# 08_Peripherals.net
KiCad netlist of a schematic drawn in Altium Designer
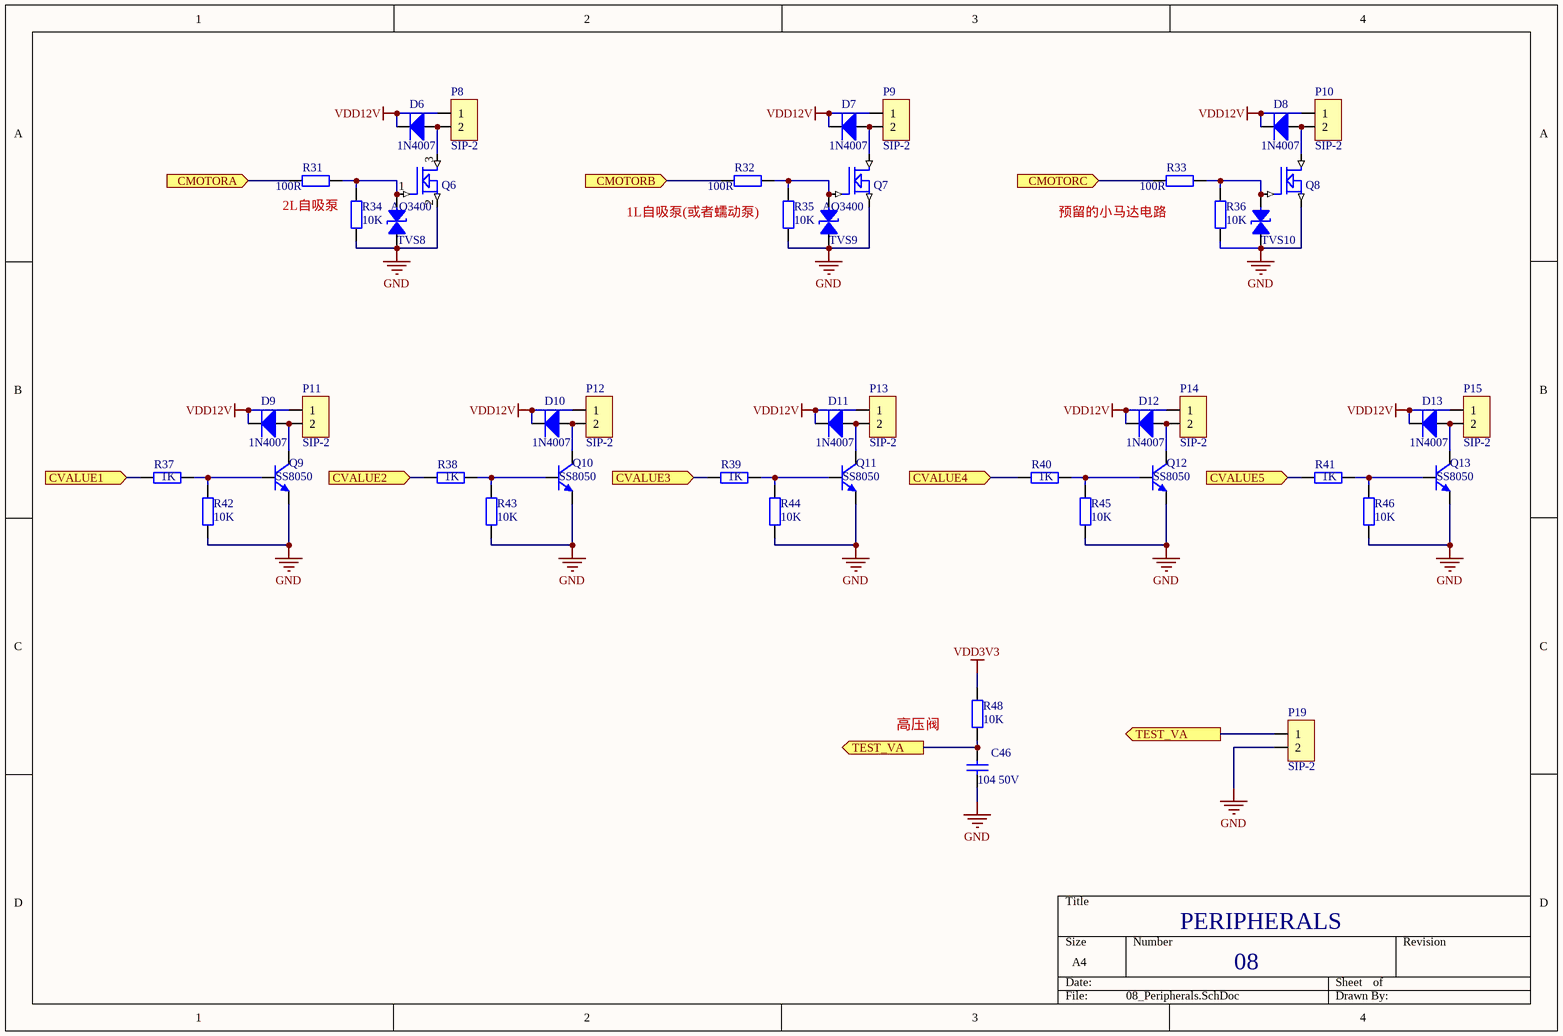
[diagram p0: 08_Peripherals.SchDoc]

(export (version "E")
  (design (tool "Eeschema 10.0.6"))
  (components
    (comp (ref "C46")
      (value "104 50V")
      (footprint "SMD-0603C")
      (description "贴片电容 10%")
      (libsource (lib "XiaoyI") (part "CAP4"))
    )
    (comp (ref "D6")
      (value "1N4007")
      (footprint "DO-214-AC")
      (description "贴片二极管")
      (libsource (lib "XiaoyI") (part "DIODE2"))
    )
    (comp (ref "D7")
      (value "1N4007")
      (footprint "DO-214-AC")
      (description "贴片二极管")
      (libsource (lib "XiaoyI") (part "DIODE2"))
    )
    (comp (ref "D8")
      (value "1N4007")
      (footprint "DO-214-AC")
      (description "贴片二极管")
      (libsource (lib "XiaoyI") (part "DIODE2"))
    )
    (comp (ref "D9")
      (value "1N4007")
      (footprint "DO-214-AC")
      (description "贴片二极管")
      (libsource (lib "XiaoyI") (part "DIODE2"))
    )
    (comp (ref "D10")
      (value "1N4007")
      (footprint "DO-214-AC")
      (description "贴片二极管")
      (libsource (lib "XiaoyI") (part "DIODE2"))
    )
    (comp (ref "D11")
      (value "1N4007")
      (footprint "DO-214-AC")
      (description "贴片二极管")
      (libsource (lib "XiaoyI") (part "DIODE2"))
    )
    (comp (ref "D12")
      (value "1N4007")
      (footprint "DO-214-AC")
      (description "贴片二极管")
      (libsource (lib "XiaoyI") (part "DIODE2"))
    )
    (comp (ref "D13")
      (value "1N4007")
      (footprint "DO-214-AC")
      (description "贴片二极管")
      (libsource (lib "XiaoyI") (part "DIODE2"))
    )
    (comp (ref "P8")
      (value "SIP-2")
      (footprint "XH-2.54-2P-LI")
      (description "XH2.54 2P 立贴")
      (libsource (lib "XiaoyI") (part "SIP-2"))
    )
    (comp (ref "P9")
      (value "SIP-2")
      (footprint "XH-2.54-2P-LI")
      (description "XH2.54 2P 立贴")
      (libsource (lib "XiaoyI") (part "SIP-2"))
    )
    (comp (ref "P10")
      (value "SIP-2")
      (footprint "XH-2.54-2P-LI")
      (description "XH2.54 2P 立贴")
      (libsource (lib "XiaoyI") (part "SIP-2"))
    )
    (comp (ref "P11")
      (value "SIP-2")
      (footprint "XH-2.54-2P-LI")
      (description "XH2.54 2P 立贴")
      (libsource (lib "XiaoyI") (part "SIP-2"))
    )
    (comp (ref "P12")
      (value "SIP-2")
      (footprint "XH-2.54-2P-LI")
      (description "XH2.54 2P 立贴")
      (libsource (lib "XiaoyI") (part "SIP-2"))
    )
    (comp (ref "P13")
      (value "SIP-2")
      (footprint "XH-2.54-2P-LI")
      (description "XH2.54 2P 立贴")
      (libsource (lib "XiaoyI") (part "SIP-2"))
    )
    (comp (ref "P14")
      (value "SIP-2")
      (footprint "XH-2.54-2P-LI")
      (description "XH2.54 2P 立贴")
      (libsource (lib "XiaoyI") (part "SIP-2"))
    )
    (comp (ref "P15")
      (value "SIP-2")
      (footprint "XH-2.54-2P-LI")
      (description "XH2.54 2P 立贴")
      (libsource (lib "XiaoyI") (part "SIP-2"))
    )
    (comp (ref "P19")
      (value "SIP-2")
      (footprint "XH-2.54-2P-LI")
      (description "XH2.54 2P 立贴")
      (libsource (lib "XiaoyI") (part "SIP-2"))
    )
    (comp (ref "Q6")
      (value "AO3400")
      (footprint "SOT-23")
      (description "MOSFET N")
      (libsource (lib "") (part "MOSFET N_1"))
    )
    (comp (ref "Q7")
      (value "AO3400")
      (footprint "SOT-23")
      (description "MOSFET N")
      (libsource (lib "XiaoyI") (part "MOSFET N"))
    )
    (comp (ref "Q8")
      (value "AO3400")
      (footprint "SOT-23")
      (description "MOSFET N")
      (libsource (lib "XiaoyI") (part "MOSFET N"))
    )
    (comp (ref "Q9")
      (value "SS8050")
      (footprint "SOT-23")
      (description "三极管")
      (libsource (lib "XiaoyI") (part "NPN-1"))
    )
    (comp (ref "Q10")
      (value "SS8050")
      (footprint "SOT-23")
      (description "三极管")
      (libsource (lib "XiaoyI") (part "NPN-1"))
    )
    (comp (ref "Q11")
      (value "SS8050")
      (footprint "SOT-23")
      (description "三极管")
      (libsource (lib "XiaoyI") (part "NPN-1"))
    )
    (comp (ref "Q12")
      (value "SS8050")
      (footprint "SOT-23")
      (description "三极管")
      (libsource (lib "XiaoyI") (part "NPN-1"))
    )
    (comp (ref "Q13")
      (value "SS8050")
      (footprint "SOT-23")
      (description "三极管")
      (libsource (lib "XiaoyI") (part "NPN-1"))
    )
    (comp (ref "R31")
      (value "100R")
      (footprint "SMD-0603")
      (description "贴片电阻 5%")
      (libsource (lib "XiaoyI") (part "RES-SOP"))
    )
    (comp (ref "R32")
      (value "100R")
      (footprint "SMD-0603")
      (description "贴片电阻 5%")
      (libsource (lib "XiaoyI") (part "RES-SOP"))
    )
    (comp (ref "R33")
      (value "100R")
      (footprint "SMD-0603")
      (description "贴片电阻 5%")
      (libsource (lib "XiaoyI") (part "RES-SOP"))
    )
    (comp (ref "R34")
      (value "10K")
      (footprint "SMD-0603")
      (description "贴片电阻 5%")
      (libsource (lib "") (part "RES-SOP_1"))
    )
    (comp (ref "R35")
      (value "10K")
      (footprint "SMD-0603")
      (description "贴片电阻 5%")
      (libsource (lib "") (part "RES-SOP_1"))
    )
    (comp (ref "R36")
      (value "10K")
      (footprint "SMD-0603")
      (description "贴片电阻 5%")
      (libsource (lib "") (part "RES-SOP_1"))
    )
    (comp (ref "R37")
      (value "1K")
      (footprint "SMD-0603")
      (description "贴片电阻 5%")
      (libsource (lib "XiaoyI") (part "RES-SOP"))
    )
    (comp (ref "R38")
      (value "1K")
      (footprint "SMD-0603")
      (description "贴片电阻 5%")
      (libsource (lib "XiaoyI") (part "RES-SOP"))
    )
    (comp (ref "R39")
      (value "1K")
      (footprint "SMD-0603")
      (description "贴片电阻 5%")
      (libsource (lib "XiaoyI") (part "RES-SOP"))
    )
    (comp (ref "R40")
      (value "1K")
      (footprint "SMD-0603")
      (description "贴片电阻 5%")
      (libsource (lib "XiaoyI") (part "RES-SOP"))
    )
    (comp (ref "R41")
      (value "1K")
      (footprint "SMD-0603")
      (description "贴片电阻 5%")
      (libsource (lib "XiaoyI") (part "RES-SOP"))
    )
    (comp (ref "R42")
      (value "10K")
      (footprint "SMD-0603")
      (description "贴片电阻 5%")
      (libsource (lib "") (part "RES-SOP_1"))
    )
    (comp (ref "R43")
      (value "10K")
      (footprint "SMD-0603")
      (description "贴片电阻 5%")
      (libsource (lib "") (part "RES-SOP_1"))
    )
    (comp (ref "R44")
      (value "10K")
      (footprint "SMD-0603")
      (description "贴片电阻 5%")
      (libsource (lib "") (part "RES-SOP_1"))
    )
    (comp (ref "R45")
      (value "10K")
      (footprint "SMD-0603")
      (description "贴片电阻 5%")
      (libsource (lib "") (part "RES-SOP_1"))
    )
    (comp (ref "R46")
      (value "10K")
      (footprint "SMD-0603")
      (description "贴片电阻 5%")
      (libsource (lib "") (part "RES-SOP_1"))
    )
    (comp (ref "R48")
      (value "10K")
      (footprint "SMD-0603")
      (description "贴片电阻 5%")
      (libsource (lib "") (part "RES-SOP_2"))
    )
    (comp (ref "TVS8")
      (value "ESD5Z5.0CT1G")
      (footprint "SOD-523")
      (description "TVS")
      (libsource (lib "XiaoyI") (part "TVS-1"))
    )
    (comp (ref "TVS9")
      (value "ESD5Z5.0CT1G")
      (footprint "SOD-523")
      (description "TVS")
      (libsource (lib "XiaoyI") (part "TVS-1"))
    )
    (comp (ref "TVS10")
      (value "ESD5Z5.0CT1G")
      (footprint "SOD-523")
      (description "TVS")
      (libsource (lib "XiaoyI") (part "TVS-1"))
    )
  )
  (nets
    (net (code "1") (name "/CMOTORA") (class "Default")
      (node (ref "R31") (pin "2") (pinfunction "2_2") (pintype "passive"))
    )
    (net (code "2") (name "/CMOTORB") (class "Default")
      (node (ref "R32") (pin "2") (pinfunction "2_2") (pintype "passive"))
    )
    (net (code "3") (name "/CMOTORC") (class "Default")
      (node (ref "R33") (pin "2") (pinfunction "2_2") (pintype "passive"))
    )
    (net (code "4") (name "/CVALUE1") (class "Default")
      (node (ref "R37") (pin "2") (pinfunction "2_2") (pintype "passive"))
    )
    (net (code "5") (name "/CVALUE2") (class "Default")
      (node (ref "R38") (pin "2") (pinfunction "2_2") (pintype "passive"))
    )
    (net (code "6") (name "/CVALUE3") (class "Default")
      (node (ref "R39") (pin "2") (pinfunction "2_2") (pintype "passive"))
    )
    (net (code "7") (name "/CVALUE4") (class "Default")
      (node (ref "R40") (pin "2") (pinfunction "2_2") (pintype "passive"))
    )
    (net (code "8") (name "/CVALUE5") (class "Default")
      (node (ref "R41") (pin "2") (pinfunction "2_2") (pintype "passive"))
    )
    (net (code "9") (name "/TEST_VA") (class "Default")
      (node (ref "C46") (pin "2") (pinfunction "2_2") (pintype "passive"))
      (node (ref "P19") (pin "1") (pinfunction "1_1") (pintype "passive"))
      (node (ref "R48") (pin "1") (pinfunction "1_1") (pintype "passive"))
    )
    (net (code "10") (name "GND") (class "Default")
      (node (ref "C46") (pin "1") (pinfunction "1_1") (pintype "passive"))
      (node (ref "P19") (pin "2") (pinfunction "2_2") (pintype "passive"))
      (node (ref "Q10") (pin "2") (pinfunction "E_2") (pintype "passive"))
      (node (ref "Q11") (pin "2") (pinfunction "E_2") (pintype "passive"))
      (node (ref "Q12") (pin "2") (pinfunction "E_2") (pintype "passive"))
      (node (ref "Q13") (pin "2") (pinfunction "E_2") (pintype "passive"))
      (node (ref "Q6") (pin "2") (pinfunction "S_2") (pintype "output"))
      (node (ref "Q7") (pin "2") (pinfunction "S_2") (pintype "output"))
      (node (ref "Q8") (pin "2") (pinfunction "S_2") (pintype "output"))
      (node (ref "Q9") (pin "2") (pinfunction "E_2") (pintype "passive"))
      (node (ref "R34") (pin "2") (pinfunction "2_2") (pintype "passive"))
      (node (ref "R35") (pin "2") (pinfunction "2_2") (pintype "passive"))
      (node (ref "R36") (pin "2") (pinfunction "2_2") (pintype "passive"))
      (node (ref "R42") (pin "2") (pinfunction "2_2") (pintype "passive"))
      (node (ref "R43") (pin "2") (pinfunction "2_2") (pintype "passive"))
      (node (ref "R44") (pin "2") (pinfunction "2_2") (pintype "passive"))
      (node (ref "R45") (pin "2") (pinfunction "2_2") (pintype "passive"))
      (node (ref "R46") (pin "2") (pinfunction "2_2") (pintype "passive"))
      (node (ref "TVS10") (pin "1") (pinfunction "A_1") (pintype "passive"))
      (node (ref "TVS8") (pin "1") (pinfunction "A_1") (pintype "passive"))
      (node (ref "TVS9") (pin "1") (pinfunction "A_1") (pintype "passive"))
    )
    (net (code "11") (name "Net-(D6-A)") (class "Default")
      (node (ref "D6") (pin "1") (pinfunction "A_1") (pintype "passive"))
      (node (ref "P8") (pin "2") (pinfunction "2_2") (pintype "passive"))
      (node (ref "Q6") (pin "3") (pinfunction "D_3") (pintype "input"))
    )
    (net (code "12") (name "Net-(D7-A)") (class "Default")
      (node (ref "D7") (pin "1") (pinfunction "A_1") (pintype "passive"))
      (node (ref "P9") (pin "2") (pinfunction "2_2") (pintype "passive"))
      (node (ref "Q7") (pin "3") (pinfunction "D_3") (pintype "input"))
    )
    (net (code "13") (name "Net-(D8-A)") (class "Default")
      (node (ref "D8") (pin "1") (pinfunction "A_1") (pintype "passive"))
      (node (ref "P10") (pin "2") (pinfunction "2_2") (pintype "passive"))
      (node (ref "Q8") (pin "3") (pinfunction "D_3") (pintype "input"))
    )
    (net (code "14") (name "Net-(D9-A)") (class "Default")
      (node (ref "D9") (pin "1") (pinfunction "A_1") (pintype "passive"))
      (node (ref "P11") (pin "2") (pinfunction "2_2") (pintype "passive"))
      (node (ref "Q9") (pin "3") (pinfunction "C_3") (pintype "passive"))
    )
    (net (code "15") (name "Net-(D10-A)") (class "Default")
      (node (ref "D10") (pin "1") (pinfunction "A_1") (pintype "passive"))
      (node (ref "P12") (pin "2") (pinfunction "2_2") (pintype "passive"))
      (node (ref "Q10") (pin "3") (pinfunction "C_3") (pintype "passive"))
    )
    (net (code "16") (name "Net-(D11-A)") (class "Default")
      (node (ref "D11") (pin "1") (pinfunction "A_1") (pintype "passive"))
      (node (ref "P13") (pin "2") (pinfunction "2_2") (pintype "passive"))
      (node (ref "Q11") (pin "3") (pinfunction "C_3") (pintype "passive"))
    )
    (net (code "17") (name "Net-(D12-A)") (class "Default")
      (node (ref "D12") (pin "1") (pinfunction "A_1") (pintype "passive"))
      (node (ref "P14") (pin "2") (pinfunction "2_2") (pintype "passive"))
      (node (ref "Q12") (pin "3") (pinfunction "C_3") (pintype "passive"))
    )
    (net (code "18") (name "Net-(D13-A)") (class "Default")
      (node (ref "D13") (pin "1") (pinfunction "A_1") (pintype "passive"))
      (node (ref "P15") (pin "2") (pinfunction "2_2") (pintype "passive"))
      (node (ref "Q13") (pin "3") (pinfunction "C_3") (pintype "passive"))
    )
    (net (code "19") (name "Net-(Q6-G)") (class "Default")
      (node (ref "Q6") (pin "1") (pinfunction "G_1") (pintype "input"))
      (node (ref "R31") (pin "1") (pinfunction "1_1") (pintype "passive"))
      (node (ref "R34") (pin "1") (pinfunction "1_1") (pintype "passive"))
      (node (ref "TVS8") (pin "2") (pinfunction "B_2") (pintype "passive"))
    )
    (net (code "20") (name "Net-(Q7-G)") (class "Default")
      (node (ref "Q7") (pin "1") (pinfunction "G_1") (pintype "input"))
      (node (ref "R32") (pin "1") (pinfunction "1_1") (pintype "passive"))
      (node (ref "R35") (pin "1") (pinfunction "1_1") (pintype "passive"))
      (node (ref "TVS9") (pin "2") (pinfunction "B_2") (pintype "passive"))
    )
    (net (code "21") (name "Net-(Q8-G)") (class "Default")
      (node (ref "Q8") (pin "1") (pinfunction "G_1") (pintype "input"))
      (node (ref "R33") (pin "1") (pinfunction "1_1") (pintype "passive"))
      (node (ref "R36") (pin "1") (pinfunction "1_1") (pintype "passive"))
      (node (ref "TVS10") (pin "2") (pinfunction "B_2") (pintype "passive"))
    )
    (net (code "22") (name "Net-(Q9-B)") (class "Default")
      (node (ref "Q9") (pin "1") (pinfunction "B_1") (pintype "passive"))
      (node (ref "R37") (pin "1") (pinfunction "1_1") (pintype "passive"))
      (node (ref "R42") (pin "1") (pinfunction "1_1") (pintype "passive"))
    )
    (net (code "23") (name "Net-(Q10-B)") (class "Default")
      (node (ref "Q10") (pin "1") (pinfunction "B_1") (pintype "passive"))
      (node (ref "R38") (pin "1") (pinfunction "1_1") (pintype "passive"))
      (node (ref "R43") (pin "1") (pinfunction "1_1") (pintype "passive"))
    )
    (net (code "24") (name "Net-(Q11-B)") (class "Default")
      (node (ref "Q11") (pin "1") (pinfunction "B_1") (pintype "passive"))
      (node (ref "R39") (pin "1") (pinfunction "1_1") (pintype "passive"))
      (node (ref "R44") (pin "1") (pinfunction "1_1") (pintype "passive"))
    )
    (net (code "25") (name "Net-(Q12-B)") (class "Default")
      (node (ref "Q12") (pin "1") (pinfunction "B_1") (pintype "passive"))
      (node (ref "R40") (pin "1") (pinfunction "1_1") (pintype "passive"))
      (node (ref "R45") (pin "1") (pinfunction "1_1") (pintype "passive"))
    )
    (net (code "26") (name "Net-(Q13-B)") (class "Default")
      (node (ref "Q13") (pin "1") (pinfunction "B_1") (pintype "passive"))
      (node (ref "R41") (pin "1") (pinfunction "1_1") (pintype "passive"))
      (node (ref "R46") (pin "1") (pinfunction "1_1") (pintype "passive"))
    )
    (net (code "27") (name "VDD3V3") (class "Default")
      (node (ref "R48") (pin "2") (pinfunction "2_2") (pintype "passive"))
    )
    (net (code "28") (name "VDD12V") (class "Default")
      (node (ref "D10") (pin "2") (pinfunction "K_2") (pintype "passive"))
      (node (ref "D11") (pin "2") (pinfunction "K_2") (pintype "passive"))
      (node (ref "D12") (pin "2") (pinfunction "K_2") (pintype "passive"))
      (node (ref "D13") (pin "2") (pinfunction "K_2") (pintype "passive"))
      (node (ref "D6") (pin "2") (pinfunction "K_2") (pintype "passive"))
      (node (ref "D7") (pin "2") (pinfunction "K_2") (pintype "passive"))
      (node (ref "D8") (pin "2") (pinfunction "K_2") (pintype "passive"))
      (node (ref "D9") (pin "2") (pinfunction "K_2") (pintype "passive"))
      (node (ref "P10") (pin "1") (pinfunction "1_1") (pintype "passive"))
      (node (ref "P11") (pin "1") (pinfunction "1_1") (pintype "passive"))
      (node (ref "P12") (pin "1") (pinfunction "1_1") (pintype "passive"))
      (node (ref "P13") (pin "1") (pinfunction "1_1") (pintype "passive"))
      (node (ref "P14") (pin "1") (pinfunction "1_1") (pintype "passive"))
      (node (ref "P15") (pin "1") (pinfunction "1_1") (pintype "passive"))
      (node (ref "P8") (pin "1") (pinfunction "1_1") (pintype "passive"))
      (node (ref "P9") (pin "1") (pinfunction "1_1") (pintype "passive"))
    )
  )
)
